# Display.net
KiCad netlist of a schematic drawn in Altium Designer
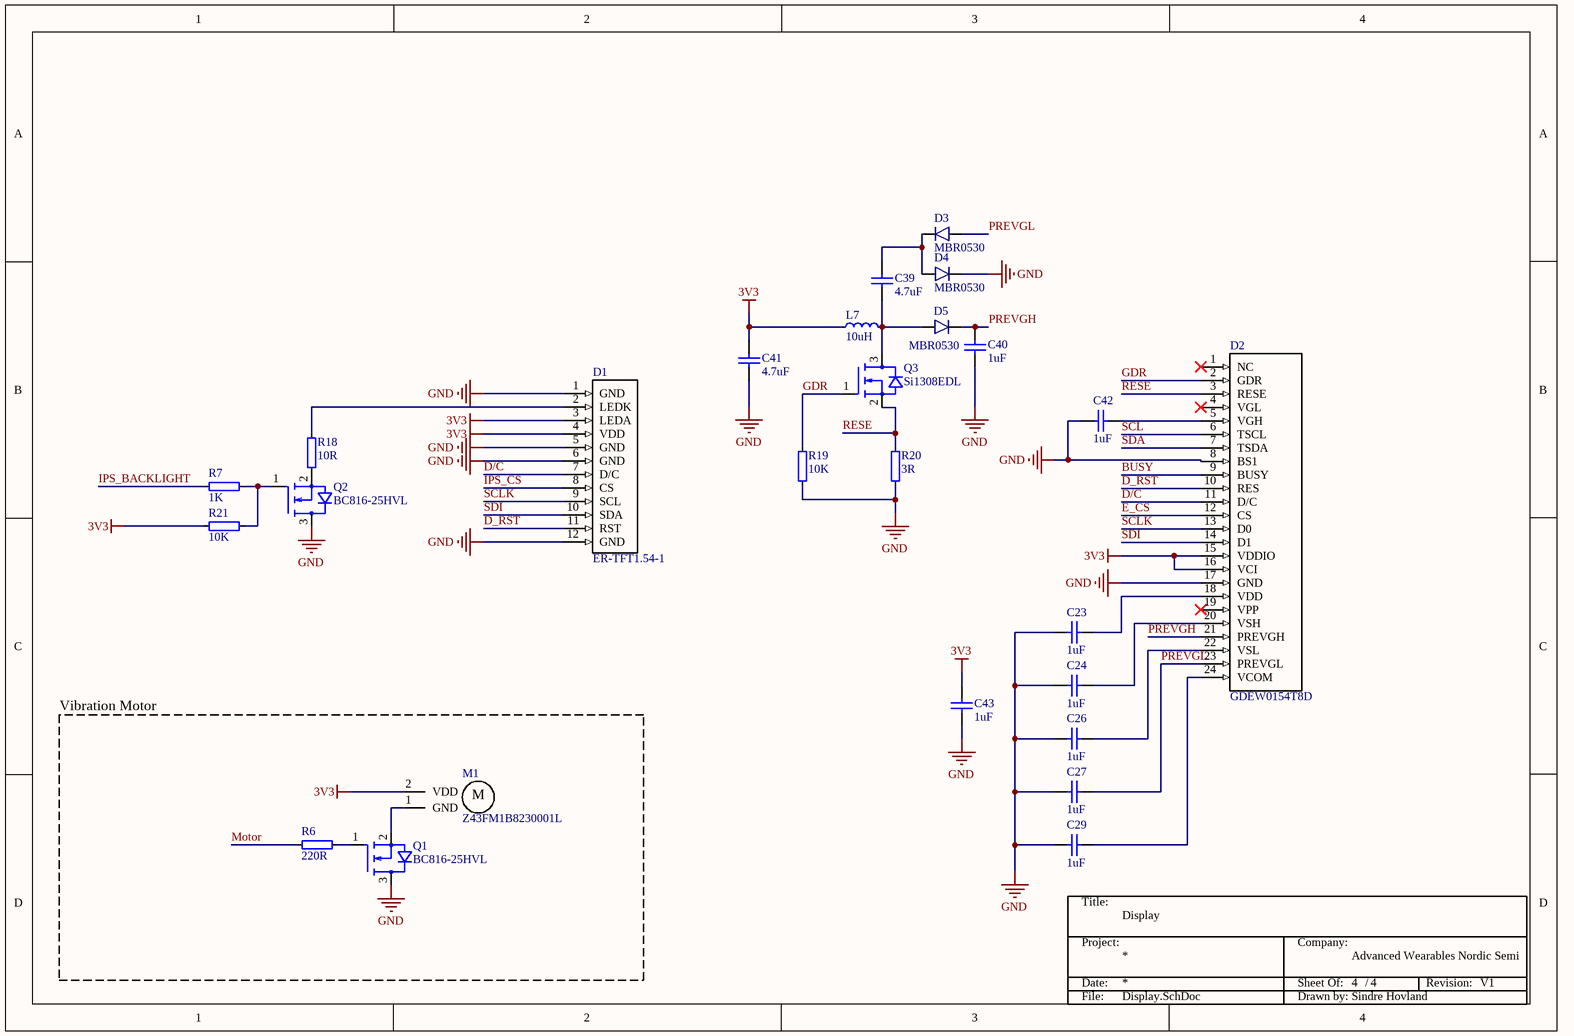
[diagram p0: Display.SchDoc]

(export (version "E")
  (design (tool "Eeschema 10.0.6"))
  (components
    (comp (ref "*") (value "TitleBlock") (libsource (lib "MISC") (part "TitleBlock")))
    (comp (ref "C23")
      (value "1uF")
      (footprint "C0402")
      (description "Capacitor")
      (fields (field (name "PUBLISHER") "Altium Limited"))
      (libsource (lib "Passives") (part "CAP"))
    )
    (comp (ref "C24")
      (value "1uF")
      (footprint "C0402")
      (description "Capacitor")
      (fields (field (name "PUBLISHER") "Altium Limited"))
      (libsource (lib "Passives") (part "CAP"))
    )
    (comp (ref "C26")
      (value "1uF")
      (footprint "C0402")
      (description "Capacitor")
      (fields (field (name "PUBLISHER") "Altium Limited"))
      (libsource (lib "Passives") (part "CAP"))
    )
    (comp (ref "C27")
      (value "1uF")
      (footprint "C0402")
      (description "Capacitor")
      (fields (field (name "PUBLISHER") "Altium Limited"))
      (libsource (lib "Passives") (part "CAP"))
    )
    (comp (ref "C29")
      (value "1uF")
      (footprint "C0402")
      (description "Capacitor")
      (fields (field (name "PUBLISHER") "Altium Limited"))
      (libsource (lib "Passives") (part "CAP"))
    )
    (comp (ref "C39")
      (value "4.7uF")
      (footprint "C0402")
      (description "Capacitor")
      (fields (field (name "PUBLISHER") "Altium Limited"))
      (libsource (lib "Passives") (part "CAP"))
    )
    (comp (ref "C40")
      (value "1uF")
      (footprint "C0402")
      (description "Capacitor")
      (fields (field (name "PUBLISHER") "Altium Limited"))
      (libsource (lib "Passives") (part "CAP"))
    )
    (comp (ref "C41")
      (value "4.7uF")
      (footprint "C0402")
      (description "Capacitor")
      (fields (field (name "PUBLISHER") "Altium Limited"))
      (libsource (lib "Passives") (part "CAP"))
    )
    (comp (ref "C42")
      (value "1uF")
      (footprint "C0402")
      (description "Capacitor")
      (fields (field (name "PUBLISHER") "Altium Limited"))
      (libsource (lib "Passives") (part "CAP"))
    )
    (comp (ref "C43")
      (value "1uF")
      (footprint "C0402")
      (description "Capacitor")
      (fields (field (name "PUBLISHER") "Altium Limited"))
      (libsource (lib "Passives") (part "CAP"))
    )
    (comp (ref "D1")
      (value "ER-TFT1.54-1")
      (footprint "IPS 1.54 inches")
      (description "IPS display 1.54 inch SPI")
      (libsource (lib "MISC") (part "IPS 1.54 inch"))
    )
    (comp (ref "D2")
      (value "GDEW0154T8D")
      (footprint "E-Papaer 1.54inches")
      (description "E-Paper 1.54 inch with integrated driver")
      (libsource (lib "MISC") (part "E-Paper 1.54 inch"))
    )
    (comp (ref "D3")
      (value "MBR0530")
      (footprint "SOD-123")
      (description "Switch-mode Schottky\r\nPower Rectifier\r\n250 V, 40 A")
      (libsource (lib "Passives") (part "Diode"))
    )
    (comp (ref "D4")
      (value "MBR0530")
      (footprint "SOD-123")
      (description "Switch-mode Schottky\r\nPower Rectifier\r\n250 V, 40 A")
      (libsource (lib "Passives") (part "Diode"))
    )
    (comp (ref "D5")
      (value "MBR0530")
      (footprint "SOD-123")
      (description "Switch-mode Schottky\r\nPower Rectifier\r\n250 V, 40 A")
      (libsource (lib "Passives") (part "Diode"))
    )
    (comp (ref "L7")
      (value "10uH")
      (footprint "IND0402")
      (description "Inductor")
      (fields
        (field (name "PART NUMBER") "FB0402-120R@100M-500mA")
        (field (name "MANUFACTURER") "Murata")
        (field (name "PUBLISHER") "Nordic Semiconductor")
      )
      (libsource (lib "Passives") (part "IND"))
    )
    (comp (ref "M1")
      (value "Z43FM1B8230001L")
      (footprint "Z43FM1B8230001L")
      (libsource (lib "MISC") (part "Vibration Motor"))
    )
    (comp (ref "Q1")
      (value "BC816-25HVL")
      (footprint "SOT23-3")
      (description "N-Channel 20V 100mA _Ta_ 150mW _Ta_ Surface Mount VMT3")
      (fields (field (name "MF") "Rohm") (field (name "DIGI-KEY_PART_NUMBER") "RUM001L02T2CLCT-ND"))
      (libsource (lib "MCU") (part "Transistor"))
    )
    (comp (ref "Q2")
      (value "BC816-25HVL")
      (footprint "SOT23-3")
      (description "N-Channel 20V 100mA _Ta_ 150mW _Ta_ Surface Mount VMT3")
      (fields (field (name "MF") "Rohm") (field (name "DIGI-KEY_PART_NUMBER") "RUM001L02T2CLCT-ND"))
      (libsource (lib "MCU") (part "Transistor"))
    )
    (comp (ref "Q3")
      (value "Si1308EDL")
      (footprint "SOT323")
      (description "N-Channel 20V 100mA _Ta_ 150mW _Ta_ Surface Mount VMT3")
      (fields (field (name "MF") "Rohm") (field (name "DIGI-KEY_PART_NUMBER") "RUM001L02T2CLCT-ND"))
      (libsource (lib "") (part "Transistor_1"))
    )
    (comp (ref "R6")
      (value "220R")
      (footprint "RES0603R")
      (description "Resistor, ±5%, 0.05W")
      (fields (field (name "PART NUMBER") "R0201-0R") (field (name "PUBLISHER") "Nordic Semiconductor"))
      (libsource (lib "Passives") (part "RES"))
    )
    (comp (ref "R7")
      (value "1K")
      (footprint "RES0402")
      (description "Resistor, ±5%, 0.05W")
      (fields (field (name "PART NUMBER") "R0201-0R") (field (name "PUBLISHER") "Nordic Semiconductor"))
      (libsource (lib "Passives") (part "RES"))
    )
    (comp (ref "R18")
      (value "10R")
      (footprint "RES0402")
      (description "Resistor, ±5%, 0.05W")
      (fields (field (name "PART NUMBER") "R0201-0R") (field (name "PUBLISHER") "Nordic Semiconductor"))
      (libsource (lib "Passives") (part "RES"))
    )
    (comp (ref "R19")
      (value "10K")
      (footprint "RES0402")
      (description "Resistor, ±5%, 0.05W")
      (fields (field (name "PART NUMBER") "R0201-0R") (field (name "PUBLISHER") "Nordic Semiconductor"))
      (libsource (lib "Passives") (part "RES"))
    )
    (comp (ref "R20")
      (value "3R")
      (footprint "RES0402")
      (description "Resistor, ±5%, 0.05W")
      (fields (field (name "PART NUMBER") "R0201-0R") (field (name "PUBLISHER") "Nordic Semiconductor"))
      (libsource (lib "Passives") (part "RES"))
    )
    (comp (ref "R21")
      (value "10K")
      (footprint "RES0402")
      (description "Resistor, ±5%, 0.05W")
      (fields (field (name "PART NUMBER") "R0201-0R") (field (name "PUBLISHER") "Nordic Semiconductor"))
      (libsource (lib "Passives") (part "RES"))
    )
  )
  (nets
    (net (code "1") (name "/BUSY") (class "Default")
      (node (ref "D2") (pin "9") (pinfunction "BUSY_9") (pintype "input"))
    )
    (net (code "2") (name "/D_RST") (class "Default")
      (node (ref "D1") (pin "11") (pinfunction "RST_11") (pintype "input"))
      (node (ref "D2") (pin "10") (pinfunction "RES_10") (pintype "input"))
    )
    (net (code "3") (name "/D{slash}C") (class "Default")
      (node (ref "D1") (pin "7") (pinfunction "D/C_7") (pintype "input"))
      (node (ref "D2") (pin "11") (pinfunction "D/C_11") (pintype "input"))
    )
    (net (code "4") (name "/E_CS") (class "Default")
      (node (ref "D2") (pin "12") (pinfunction "CS_12") (pintype "input"))
    )
    (net (code "5") (name "/GDR") (class "Default")
      (node (ref "D2") (pin "2") (pinfunction "GDR_2") (pintype "input"))
      (node (ref "Q3") (pin "1") (pinfunction "G_1") (pintype "passive"))
      (node (ref "R19") (pin "2") (pinfunction "2_2") (pintype "passive"))
    )
    (net (code "6") (name "/IPS_BACKLIGHT") (class "Default")
      (node (ref "R7") (pin "1") (pinfunction "1_1") (pintype "passive"))
    )
    (net (code "7") (name "/IPS_CS") (class "Default")
      (node (ref "D1") (pin "8") (pinfunction "CS_8") (pintype "input"))
    )
    (net (code "8") (name "/Motor") (class "Default")
      (node (ref "R6") (pin "1") (pinfunction "1_1") (pintype "passive"))
    )
    (net (code "9") (name "/PREVGH") (class "Default")
      (node (ref "C40") (pin "1") (pinfunction "1_1") (pintype "passive"))
      (node (ref "D2") (pin "21") (pinfunction "PREVGH_21") (pintype "input"))
      (node (ref "D5") (pin "2") (pinfunction "C_2") (pintype "passive"))
    )
    (net (code "10") (name "/PREVGL") (class "Default")
      (node (ref "C27") (pin "1") (pinfunction "1_1") (pintype "passive"))
      (node (ref "D2") (pin "23") (pinfunction "PREVGL_23") (pintype "input"))
      (node (ref "D3") (pin "1") (pinfunction "A_1") (pintype "passive"))
    )
    (net (code "11") (name "/RESE") (class "Default")
      (node (ref "D2") (pin "3") (pinfunction "RESE_3") (pintype "input"))
      (node (ref "Q3") (pin "2") (pinfunction "S_2") (pintype "passive"))
      (node (ref "R20") (pin "2") (pinfunction "2_2") (pintype "passive"))
    )
    (net (code "12") (name "/SCL") (class "Default")
      (node (ref "D2") (pin "6") (pinfunction "TSCL_6") (pintype "input"))
    )
    (net (code "13") (name "/SCLK") (class "Default")
      (node (ref "D1") (pin "9") (pinfunction "SCL_9") (pintype "input"))
      (node (ref "D2") (pin "13") (pinfunction "D0_13") (pintype "input"))
    )
    (net (code "14") (name "/SDA") (class "Default")
      (node (ref "D2") (pin "7") (pinfunction "TSDA_7") (pintype "input"))
    )
    (net (code "15") (name "/SDI") (class "Default")
      (node (ref "D1") (pin "10") (pinfunction "SDA_10") (pintype "input"))
      (node (ref "D2") (pin "14") (pinfunction "D1_14") (pintype "input"))
    )
    (net (code "16") (name "3V3") (class "Default")
      (node (ref "C41") (pin "1") (pinfunction "1_1") (pintype "passive"))
      (node (ref "C43") (pin "1") (pinfunction "1_1") (pintype "passive"))
      (node (ref "D1") (pin "3") (pinfunction "LEDA_3") (pintype "input"))
      (node (ref "D1") (pin "4") (pinfunction "VDD_4") (pintype "input"))
      (node (ref "D2") (pin "15") (pinfunction "VDDIO_15") (pintype "input"))
      (node (ref "D2") (pin "16") (pinfunction "VCI_16") (pintype "input"))
      (node (ref "L7") (pin "1") (pinfunction "1_1") (pintype "passive"))
      (node (ref "M1") (pin "2") (pinfunction "VDD_2") (pintype "passive"))
      (node (ref "R21") (pin "1") (pinfunction "1_1") (pintype "passive"))
    )
    (net (code "17") (name "GND") (class "Default")
      (node (ref "C23") (pin "2") (pinfunction "2_2") (pintype "passive"))
      (node (ref "C24") (pin "2") (pinfunction "2_2") (pintype "passive"))
      (node (ref "C26") (pin "2") (pinfunction "2_2") (pintype "passive"))
      (node (ref "C27") (pin "2") (pinfunction "2_2") (pintype "passive"))
      (node (ref "C29") (pin "2") (pinfunction "2_2") (pintype "passive"))
      (node (ref "C40") (pin "2") (pinfunction "2_2") (pintype "passive"))
      (node (ref "C41") (pin "2") (pinfunction "2_2") (pintype "passive"))
      (node (ref "C42") (pin "1") (pinfunction "1_1") (pintype "passive"))
      (node (ref "C43") (pin "2") (pinfunction "2_2") (pintype "passive"))
      (node (ref "D1") (pin "1") (pinfunction "GND_1") (pintype "input"))
      (node (ref "D1") (pin "12") (pinfunction "GND_12") (pintype "input"))
      (node (ref "D1") (pin "5") (pinfunction "GND_5") (pintype "input"))
      (node (ref "D1") (pin "6") (pinfunction "GND_6") (pintype "input"))
      (node (ref "D2") (pin "17") (pinfunction "GND_17") (pintype "input"))
      (node (ref "D2") (pin "8") (pinfunction "BS1_8") (pintype "input"))
      (node (ref "D4") (pin "2") (pinfunction "C_2") (pintype "passive"))
      (node (ref "Q1") (pin "3") (pinfunction "D_3") (pintype "passive"))
      (node (ref "Q2") (pin "3") (pinfunction "D_3") (pintype "passive"))
      (node (ref "R19") (pin "1") (pinfunction "1_1") (pintype "passive"))
      (node (ref "R20") (pin "1") (pinfunction "1_1") (pintype "passive"))
    )
    (net (code "18") (name "Net-(D1-LEDK)") (class "Default")
      (node (ref "D1") (pin "2") (pinfunction "LEDK_2") (pintype "input"))
      (node (ref "R18") (pin "2") (pinfunction "2_2") (pintype "passive"))
    )
    (net (code "19") (name "Net-(D2-VCOM)") (class "Default")
      (node (ref "C29") (pin "1") (pinfunction "1_1") (pintype "passive"))
      (node (ref "D2") (pin "24") (pinfunction "VCOM_24") (pintype "input"))
    )
    (net (code "20") (name "Net-(D2-VDD)") (class "Default")
      (node (ref "C23") (pin "1") (pinfunction "1_1") (pintype "passive"))
      (node (ref "D2") (pin "18") (pinfunction "VDD_18") (pintype "input"))
    )
    (net (code "21") (name "Net-(D2-VGH)") (class "Default")
      (node (ref "C42") (pin "2") (pinfunction "2_2") (pintype "passive"))
      (node (ref "D2") (pin "5") (pinfunction "VGH_5") (pintype "input"))
    )
    (net (code "22") (name "Net-(D2-VSH)") (class "Default")
      (node (ref "C24") (pin "1") (pinfunction "1_1") (pintype "passive"))
      (node (ref "D2") (pin "20") (pinfunction "VSH_20") (pintype "input"))
    )
    (net (code "23") (name "Net-(D2-VSL)") (class "Default")
      (node (ref "C26") (pin "1") (pinfunction "1_1") (pintype "passive"))
      (node (ref "D2") (pin "22") (pinfunction "VSL_22") (pintype "input"))
    )
    (net (code "24") (name "Net-(D3-C)") (class "Default")
      (node (ref "C39") (pin "1") (pinfunction "1_1") (pintype "passive"))
      (node (ref "D3") (pin "2") (pinfunction "C_2") (pintype "passive"))
      (node (ref "D4") (pin "1") (pinfunction "A_1") (pintype "passive"))
    )
    (net (code "25") (name "Net-(D5-A)") (class "Default")
      (node (ref "C39") (pin "2") (pinfunction "2_2") (pintype "passive"))
      (node (ref "D5") (pin "1") (pinfunction "A_1") (pintype "passive"))
      (node (ref "L7") (pin "2") (pinfunction "2_2") (pintype "passive"))
      (node (ref "Q3") (pin "3") (pinfunction "D_3") (pintype "passive"))
    )
    (net (code "26") (name "Net-(M1-GND)") (class "Default")
      (node (ref "M1") (pin "1") (pinfunction "GND_1") (pintype "passive"))
      (node (ref "Q1") (pin "2") (pinfunction "S_2") (pintype "passive"))
    )
    (net (code "27") (name "Net-(Q1-G)") (class "Default")
      (node (ref "Q1") (pin "1") (pinfunction "G_1") (pintype "passive"))
      (node (ref "R6") (pin "2") (pinfunction "2_2") (pintype "passive"))
    )
    (net (code "28") (name "Net-(Q2-G)") (class "Default")
      (node (ref "Q2") (pin "1") (pinfunction "G_1") (pintype "passive"))
      (node (ref "R21") (pin "2") (pinfunction "2_2") (pintype "passive"))
      (node (ref "R7") (pin "2") (pinfunction "2_2") (pintype "passive"))
    )
    (net (code "29") (name "Net-(Q2-S)") (class "Default")
      (node (ref "Q2") (pin "2") (pinfunction "S_2") (pintype "passive"))
      (node (ref "R18") (pin "1") (pinfunction "1_1") (pintype "passive"))
    )
    (net (code "30") (name "unconnected-(D2-NC-Pad1)") (class "Default")
      (node (ref "D2") (pin "1") (pinfunction "NC_1") (pintype "input+no_connect"))
    )
    (net (code "31") (name "unconnected-(D2-VGL-Pad4)") (class "Default")
      (node (ref "D2") (pin "4") (pinfunction "VGL_4") (pintype "input+no_connect"))
    )
    (net (code "32") (name "unconnected-(D2-VPP-Pad19)") (class "Default")
      (node (ref "D2") (pin "19") (pinfunction "VPP_19") (pintype "input+no_connect"))
    )
  )
)
